# psu_2.net
KiCad netlist of a schematic drawn in EAGLE
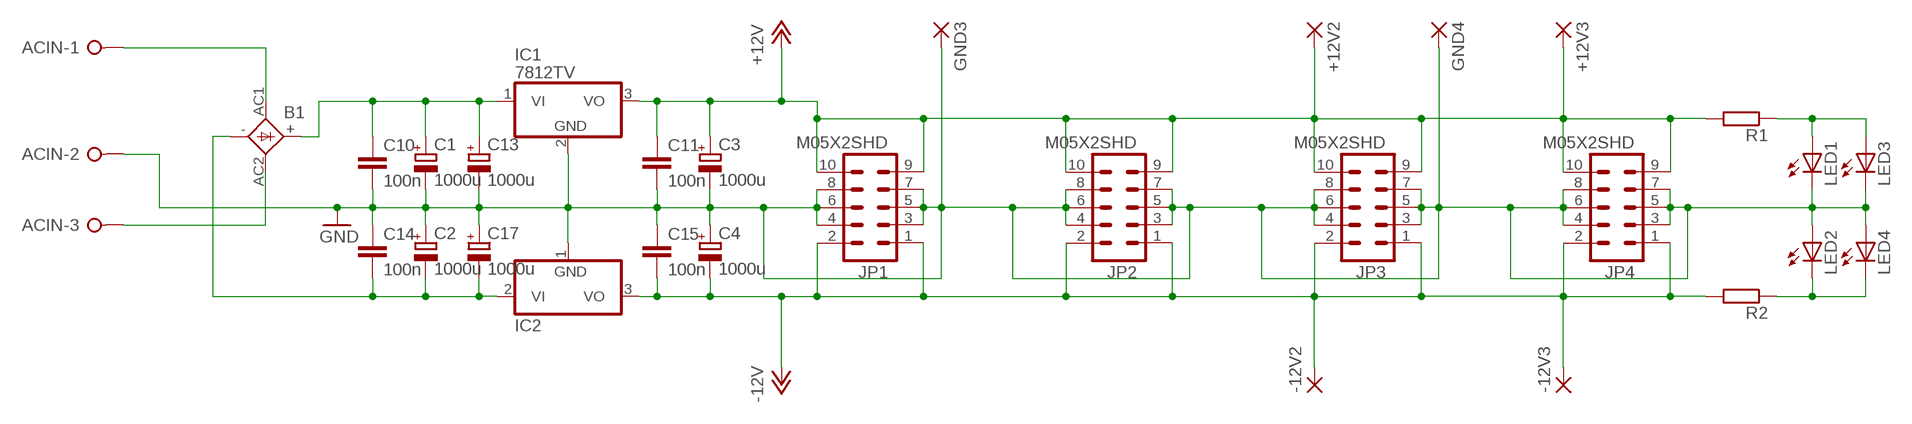
[diagram p0: schematic, sheet 1]

(export (version "E")
  (design (tool "Eeschema 10.0.6"))
  (components
    (comp (ref "+12V2")
      (value "2,54/1,0")
      (footprint "eagle-import:2,54_1,0")
      (libsource (lib "eagle-import") (part "2,54/1,0"))
    )
    (comp (ref "+12V3")
      (value "2,54/1,0")
      (footprint "eagle-import:2,54_1,0")
      (libsource (lib "eagle-import") (part "2,54/1,0"))
    )
    (comp (ref "-12V2")
      (value "2,54/1,0")
      (footprint "eagle-import:2,54_1,0")
      (libsource (lib "eagle-import") (part "2,54/1,0"))
    )
    (comp (ref "-12V3")
      (value "2,54/1,0")
      (footprint "eagle-import:2,54_1,0")
      (libsource (lib "eagle-import") (part "2,54/1,0"))
    )
    (comp (ref "ACIN")
      (value "W237-3E")
      (footprint "eagle-import:W237-3E")
      (libsource (lib "eagle-import") (part "W237-3E"))
    )
    (comp (ref "B1")
      (value "2KBP")
      (footprint "eagle-import:2KBP")
      (libsource (lib "eagle-import") (part "2KBP"))
    )
    (comp (ref "C1")
      (value "1000u")
      (footprint "eagle-import:E3,5-10")
      (libsource (lib "eagle-import") (part "CPOL-EUE3.5-10"))
    )
    (comp (ref "C2")
      (value "1000u")
      (footprint "eagle-import:E3,5-10")
      (libsource (lib "eagle-import") (part "CPOL-EUE3.5-10"))
    )
    (comp (ref "C3")
      (value "1000u")
      (footprint "eagle-import:E3,5-10")
      (libsource (lib "eagle-import") (part "CPOL-EUE3.5-10"))
    )
    (comp (ref "C4")
      (value "1000u")
      (footprint "eagle-import:E3,5-10")
      (libsource (lib "eagle-import") (part "CPOL-EUE3.5-10"))
    )
    (comp (ref "C10")
      (value "100n")
      (footprint "eagle-import:C1206K")
      (libsource (lib "eagle-import") (part "C-EUC1206K"))
    )
    (comp (ref "C11")
      (value "100n")
      (footprint "eagle-import:C1206K")
      (libsource (lib "eagle-import") (part "C-EUC1206K"))
    )
    (comp (ref "C13")
      (value "1000u")
      (footprint "eagle-import:E3,5-10")
      (libsource (lib "eagle-import") (part "CPOL-EUE3.5-10"))
    )
    (comp (ref "C14")
      (value "100n")
      (footprint "eagle-import:C1206K")
      (libsource (lib "eagle-import") (part "C-EUC1206K"))
    )
    (comp (ref "C15")
      (value "100n")
      (footprint "eagle-import:C1206K")
      (libsource (lib "eagle-import") (part "C-EUC1206K"))
    )
    (comp (ref "C17")
      (value "1000u")
      (footprint "eagle-import:E3,5-10")
      (libsource (lib "eagle-import") (part "CPOL-EUE3.5-10"))
    )
    (comp (ref "GND3")
      (value "2,54/1,0")
      (footprint "eagle-import:2,54_1,0")
      (libsource (lib "eagle-import") (part "2,54/1,0"))
    )
    (comp (ref "GND4")
      (value "2,54/1,0")
      (footprint "eagle-import:2,54_1,0")
      (libsource (lib "eagle-import") (part "2,54/1,0"))
    )
    (comp (ref "IC1")
      (value "7812TV")
      (footprint "eagle-import:TO220V")
      (libsource (lib "eagle-import") (part "78TV12"))
    )
    (comp (ref "IC2")
      (value "7912TV")
      (footprint "eagle-import:TO220V")
      (libsource (lib "eagle-import") (part "79TV12"))
    )
    (comp (ref "JP1")
      (value "M05X2SHD")
      (footprint "eagle-import:2X5-SHROUDED")
      (libsource (lib "eagle-import") (part "M05X2SHD"))
    )
    (comp (ref "JP2")
      (value "M05X2SHD")
      (footprint "eagle-import:2X5-SHROUDED")
      (libsource (lib "eagle-import") (part "M05X2SHD"))
    )
    (comp (ref "JP3")
      (value "M05X2SHD")
      (footprint "eagle-import:2X5-SHROUDED")
      (libsource (lib "eagle-import") (part "M05X2SHD"))
    )
    (comp (ref "JP4")
      (value "M05X2SHD")
      (footprint "eagle-import:2X5-SHROUDED")
      (libsource (lib "eagle-import") (part "M05X2SHD"))
    )
    (comp (ref "LED1")
      (value "LED3MM")
      (footprint "eagle-import:LED3MM")
      (libsource (lib "eagle-import") (part "LED3MM"))
    )
    (comp (ref "LED2")
      (value "LED3MM")
      (footprint "eagle-import:LED3MM")
      (libsource (lib "eagle-import") (part "LED3MM"))
    )
    (comp (ref "LED3")
      (value "LEDCHIPLED_1206")
      (footprint "eagle-import:CHIPLED_1206")
      (libsource (lib "eagle-import") (part "LEDCHIPLED_1206"))
    )
    (comp (ref "LED4")
      (value "LEDCHIPLED_1206")
      (footprint "eagle-import:CHIPLED_1206")
      (libsource (lib "eagle-import") (part "LEDCHIPLED_1206"))
    )
    (comp (ref "R1")
      (value "R-EU_M1206")
      (footprint "eagle-import:M1206")
      (libsource (lib "eagle-import") (part "R-EU_M1206"))
    )
    (comp (ref "R2")
      (value "R-EU_M1206")
      (footprint "eagle-import:M1206")
      (libsource (lib "eagle-import") (part "R-EU_M1206"))
    )
  )
  (nets
    (net (code "1") (name "+12V") (class "Default")
      (node (ref "+12V2") (pin "1") (pinfunction "P_1") (pintype "passive"))
      (node (ref "+12V3") (pin "1") (pinfunction "P_1") (pintype "passive"))
      (node (ref "C11") (pin "1") (pinfunction "1_1") (pintype "passive"))
      (node (ref "C3") (pin "+") (pinfunction "+_+") (pintype "passive"))
      (node (ref "IC1") (pin "3") (pinfunction "VO_3") (pintype "passive"))
      (node (ref "JP1") (pin "10") (pinfunction "10_10") (pintype "passive"))
      (node (ref "JP1") (pin "9") (pinfunction "9_9") (pintype "passive"))
      (node (ref "JP2") (pin "10") (pinfunction "10_10") (pintype "passive"))
      (node (ref "JP2") (pin "9") (pinfunction "9_9") (pintype "passive"))
      (node (ref "JP3") (pin "10") (pinfunction "10_10") (pintype "passive"))
      (node (ref "JP3") (pin "9") (pinfunction "9_9") (pintype "passive"))
      (node (ref "JP4") (pin "10") (pinfunction "10_10") (pintype "passive"))
      (node (ref "JP4") (pin "9") (pinfunction "9_9") (pintype "passive"))
      (node (ref "R1") (pin "2") (pinfunction "2_2") (pintype "passive"))
    )
    (net (code "2") (name "-12V") (class "Default")
      (node (ref "-12V2") (pin "1") (pinfunction "P_1") (pintype "passive"))
      (node (ref "-12V3") (pin "1") (pinfunction "P_1") (pintype "passive"))
      (node (ref "C15") (pin "2") (pinfunction "2_2") (pintype "passive"))
      (node (ref "C4") (pin "-") (pinfunction "-_-") (pintype "passive"))
      (node (ref "IC2") (pin "3") (pinfunction "VO_3") (pintype "passive"))
      (node (ref "JP1") (pin "1") (pinfunction "1_1") (pintype "passive"))
      (node (ref "JP1") (pin "2") (pinfunction "2_2") (pintype "passive"))
      (node (ref "JP2") (pin "1") (pinfunction "1_1") (pintype "passive"))
      (node (ref "JP2") (pin "2") (pinfunction "2_2") (pintype "passive"))
      (node (ref "JP3") (pin "1") (pinfunction "1_1") (pintype "passive"))
      (node (ref "JP3") (pin "2") (pinfunction "2_2") (pintype "passive"))
      (node (ref "JP4") (pin "1") (pinfunction "1_1") (pintype "passive"))
      (node (ref "JP4") (pin "2") (pinfunction "2_2") (pintype "passive"))
      (node (ref "R2") (pin "2") (pinfunction "2_2") (pintype "passive"))
    )
    (net (code "3") (name "GND") (class "Default")
      (node (ref "ACIN") (pin "2") (pinfunction "KL_2") (pintype "passive"))
      (node (ref "C1") (pin "-") (pinfunction "-_-") (pintype "passive"))
      (node (ref "C10") (pin "2") (pinfunction "2_2") (pintype "passive"))
      (node (ref "C11") (pin "2") (pinfunction "2_2") (pintype "passive"))
      (node (ref "C13") (pin "-") (pinfunction "-_-") (pintype "passive"))
      (node (ref "C14") (pin "1") (pinfunction "1_1") (pintype "passive"))
      (node (ref "C15") (pin "1") (pinfunction "1_1") (pintype "passive"))
      (node (ref "C17") (pin "+") (pinfunction "+_+") (pintype "passive"))
      (node (ref "C2") (pin "+") (pinfunction "+_+") (pintype "passive"))
      (node (ref "C3") (pin "-") (pinfunction "-_-") (pintype "passive"))
      (node (ref "C4") (pin "+") (pinfunction "+_+") (pintype "passive"))
      (node (ref "GND3") (pin "1") (pinfunction "P_1") (pintype "passive"))
      (node (ref "GND4") (pin "1") (pinfunction "P_1") (pintype "passive"))
      (node (ref "IC1") (pin "2") (pinfunction "GND_2") (pintype "passive"))
      (node (ref "IC2") (pin "1") (pinfunction "GND_1") (pintype "passive"))
      (node (ref "JP1") (pin "3") (pinfunction "3_3") (pintype "passive"))
      (node (ref "JP1") (pin "4") (pinfunction "4_4") (pintype "passive"))
      (node (ref "JP1") (pin "5") (pinfunction "5_5") (pintype "passive"))
      (node (ref "JP1") (pin "6") (pinfunction "6_6") (pintype "passive"))
      (node (ref "JP1") (pin "7") (pinfunction "7_7") (pintype "passive"))
      (node (ref "JP1") (pin "8") (pinfunction "8_8") (pintype "passive"))
      (node (ref "JP2") (pin "3") (pinfunction "3_3") (pintype "passive"))
      (node (ref "JP2") (pin "4") (pinfunction "4_4") (pintype "passive"))
      (node (ref "JP2") (pin "5") (pinfunction "5_5") (pintype "passive"))
      (node (ref "JP2") (pin "6") (pinfunction "6_6") (pintype "passive"))
      (node (ref "JP2") (pin "7") (pinfunction "7_7") (pintype "passive"))
      (node (ref "JP2") (pin "8") (pinfunction "8_8") (pintype "passive"))
      (node (ref "JP3") (pin "3") (pinfunction "3_3") (pintype "passive"))
      (node (ref "JP3") (pin "4") (pinfunction "4_4") (pintype "passive"))
      (node (ref "JP3") (pin "5") (pinfunction "5_5") (pintype "passive"))
      (node (ref "JP3") (pin "6") (pinfunction "6_6") (pintype "passive"))
      (node (ref "JP3") (pin "7") (pinfunction "7_7") (pintype "passive"))
      (node (ref "JP3") (pin "8") (pinfunction "8_8") (pintype "passive"))
      (node (ref "JP4") (pin "3") (pinfunction "3_3") (pintype "passive"))
      (node (ref "JP4") (pin "4") (pinfunction "4_4") (pintype "passive"))
      (node (ref "JP4") (pin "5") (pinfunction "5_5") (pintype "passive"))
      (node (ref "JP4") (pin "6") (pinfunction "6_6") (pintype "passive"))
      (node (ref "JP4") (pin "7") (pinfunction "7_7") (pintype "passive"))
      (node (ref "JP4") (pin "8") (pinfunction "8_8") (pintype "passive"))
      (node (ref "LED1") (pin "K") (pinfunction "C_K") (pintype "passive"))
      (node (ref "LED2") (pin "A") (pinfunction "A_A") (pintype "passive"))
      (node (ref "LED3") (pin "C") (pinfunction "C_C") (pintype "passive"))
      (node (ref "LED4") (pin "A") (pinfunction "A_A") (pintype "passive"))
    )
    (net (code "4") (name "Net-(ACINA-KL)") (class "Default")
      (node (ref "ACIN") (pin "1") (pinfunction "KL_1") (pintype "passive"))
      (node (ref "B1") (pin "AC1") (pinfunction "AC1_AC1") (pintype "passive"))
    )
    (net (code "5") (name "Net-(ACINC-KL)") (class "Default")
      (node (ref "ACIN") (pin "3") (pinfunction "KL_3") (pintype "passive"))
      (node (ref "B1") (pin "AC2") (pinfunction "AC2_AC2") (pintype "passive"))
    )
    (net (code "6") (name "Net-(IC1-VI)") (class "Default")
      (node (ref "B1") (pin "+") (pinfunction "+_+") (pintype "passive"))
      (node (ref "C1") (pin "+") (pinfunction "+_+") (pintype "passive"))
      (node (ref "C10") (pin "1") (pinfunction "1_1") (pintype "passive"))
      (node (ref "C13") (pin "+") (pinfunction "+_+") (pintype "passive"))
      (node (ref "IC1") (pin "1") (pinfunction "VI_1") (pintype "input"))
    )
    (net (code "7") (name "Net-(IC2-VI)") (class "Default")
      (node (ref "B1") (pin "-") (pinfunction "-_-") (pintype "passive"))
      (node (ref "C14") (pin "2") (pinfunction "2_2") (pintype "passive"))
      (node (ref "C17") (pin "-") (pinfunction "-_-") (pintype "passive"))
      (node (ref "C2") (pin "-") (pinfunction "-_-") (pintype "passive"))
      (node (ref "IC2") (pin "2") (pinfunction "VI_2") (pintype "input"))
    )
    (net (code "8") (name "Net-(LED1-PadA)") (class "Default")
      (node (ref "LED1") (pin "A") (pinfunction "A_A") (pintype "passive"))
      (node (ref "LED3") (pin "A") (pinfunction "A_A") (pintype "passive"))
      (node (ref "R1") (pin "1") (pinfunction "1_1") (pintype "passive"))
    )
    (net (code "9") (name "Net-(LED2-C)") (class "Default")
      (node (ref "LED2") (pin "K") (pinfunction "C_K") (pintype "passive"))
      (node (ref "LED4") (pin "C") (pinfunction "C_C") (pintype "passive"))
      (node (ref "R2") (pin "1") (pinfunction "1_1") (pintype "passive"))
    )
  )
)
